# Too_Head_PCB_REV0_3.net
KiCad netlist of a schematic drawn in Altium Designer
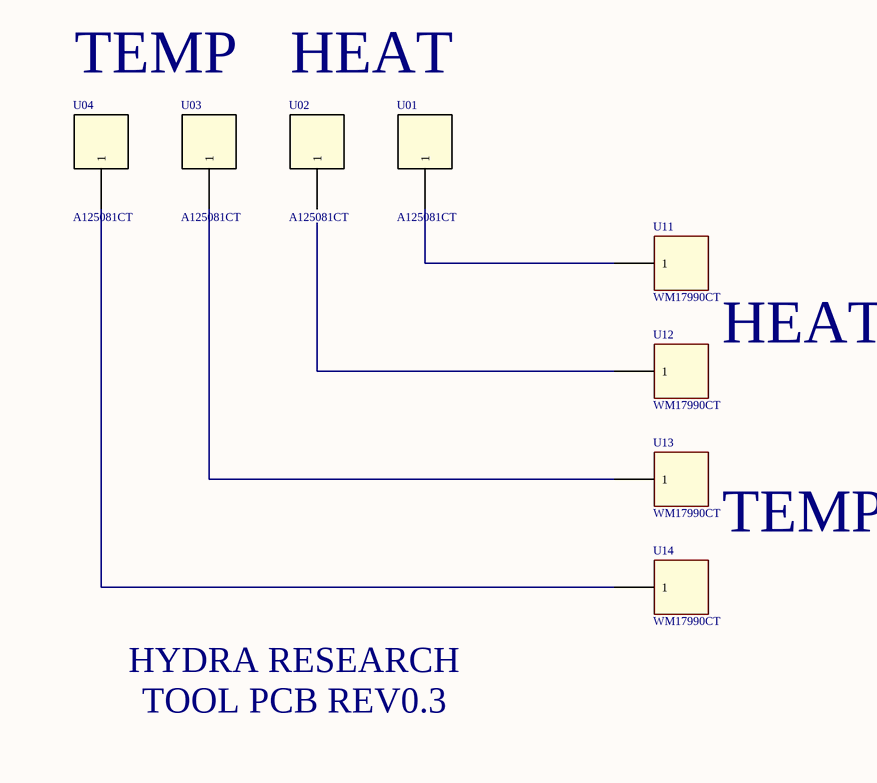
[diagram p0: Too Head PCB REV0.3.SchDoc]

(export (version "E")
  (design (tool "Eeschema 10.0.6"))
  (components
    (comp (ref "U01")
      (value "A125081CT")
      (footprint "A125081CT-ND")
      (fields (field (name "MPN") "A125081CT-ND"))
      (libsource (lib "Schlib1") (part "A125081CT"))
    )
    (comp (ref "U02")
      (value "A125081CT")
      (footprint "A125081CT-ND")
      (fields (field (name "MPN") "A125081CT-ND"))
      (libsource (lib "Schlib1") (part "A125081CT"))
    )
    (comp (ref "U03")
      (value "A125081CT")
      (footprint "A125081CT-ND")
      (fields (field (name "MPN") "A125081CT-ND"))
      (libsource (lib "Schlib1") (part "A125081CT"))
    )
    (comp (ref "U04")
      (value "A125081CT")
      (footprint "A125081CT-ND")
      (fields (field (name "MPN") "A125081CT-ND"))
      (libsource (lib "Schlib1") (part "A125081CT"))
    )
    (comp (ref "U11")
      (value "WM17990CT")
      (footprint "WM17990CT-ND-l")
      (fields (field (name "MPN") "WM17990CT-ND"))
      (libsource (lib "Schlib1") (part "WM17990CT"))
    )
    (comp (ref "U12")
      (value "WM17990CT")
      (footprint "WM17990CT-ND-l")
      (fields (field (name "MPN") "WM17990CT-ND"))
      (libsource (lib "Schlib1") (part "WM17990CT"))
    )
    (comp (ref "U13")
      (value "WM17990CT")
      (footprint "WM17990CT-ND-l")
      (fields (field (name "MPN") "WM17990CT-ND"))
      (libsource (lib "Schlib1") (part "WM17990CT"))
    )
    (comp (ref "U14")
      (value "WM17990CT")
      (footprint "WM17990CT-ND-l")
      (fields (field (name "MPN") "WM17990CT-ND"))
      (libsource (lib "Schlib1") (part "WM17990CT"))
    )
  )
  (nets
    (net (code "1") (name "Net-(U01-1)") (class "Default")
      (node (ref "U01") (pin "?") (pinfunction "1_?") (pintype "passive"))
      (node (ref "U11") (pin "?") (pinfunction "1_?") (pintype "passive"))
    )
    (net (code "2") (name "Net-(U03-1)") (class "Default")
      (node (ref "U03") (pin "?") (pinfunction "1_?") (pintype "passive"))
      (node (ref "U13") (pin "?") (pinfunction "1_?") (pintype "passive"))
    )
    (net (code "3") (name "Net-(U04-1)") (class "Default")
      (node (ref "U04") (pin "?") (pinfunction "1_?") (pintype "passive"))
      (node (ref "U14") (pin "?") (pinfunction "1_?") (pintype "passive"))
    )
    (net (code "4") (name "unconnected-(U02-1-Pad?)") (class "Default")
      (node (ref "U02") (pin "?") (pinfunction "1_?") (pintype "passive"))
    )
    (net (code "5") (name "unconnected-(U12-1-Pad?)") (class "Default")
      (node (ref "U12") (pin "?") (pinfunction "1_?") (pintype "passive"))
    )
  )
)
